# MoteinoMEGA.net
KiCad netlist of a schematic drawn in EAGLE
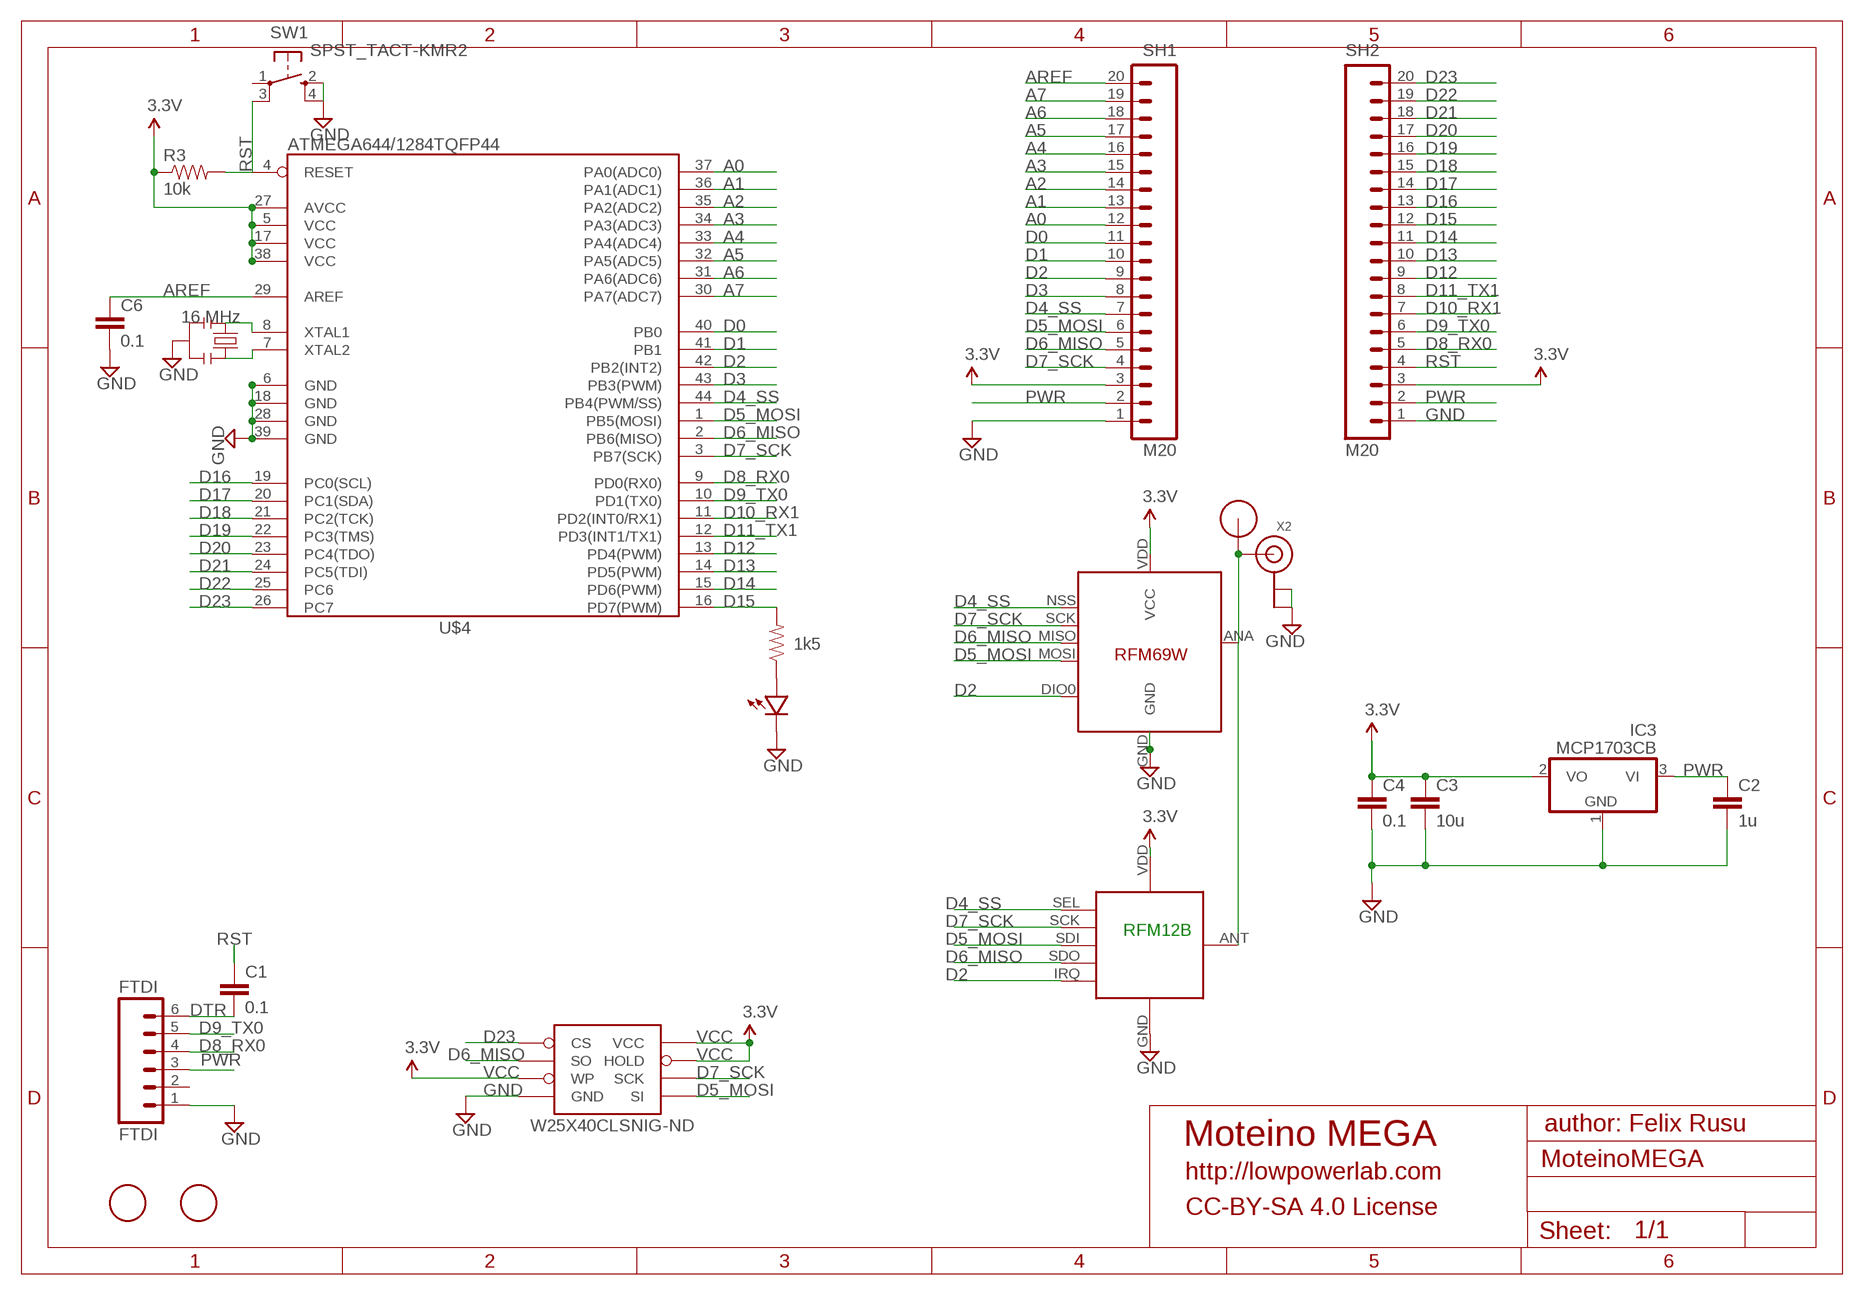
[diagram p0: schematic, sheet 1]

(export (version "E")
  (design (tool "Eeschema 10.0.6"))
  (components
    (comp (ref "C1")
      (value "0.1")
      (footprint "eagle-import:0603-CAP")
      (libsource (lib "eagle-import") (part "CAP0603-CAP"))
    )
    (comp (ref "C2")
      (value "1u")
      (footprint "eagle-import:0603-CAP")
      (libsource (lib "eagle-import") (part "CAP0603-CAP"))
    )
    (comp (ref "C3")
      (value "10u")
      (footprint "eagle-import:0805-CAP")
      (libsource (lib "eagle-import") (part "CAP0805-CAP"))
    )
    (comp (ref "C4")
      (value "0.1")
      (footprint "eagle-import:0603-CAP")
      (libsource (lib "eagle-import") (part "CAP0603-CAP"))
    )
    (comp (ref "C6")
      (value "0.1")
      (footprint "eagle-import:0603-CAP")
      (libsource (lib "eagle-import") (part "CAP0603-CAP"))
    )
    (comp (ref "FTDI")
      (value "FTDI")
      (footprint "eagle-import:1X06")
      (libsource (lib "eagle-import") (part "M06SIP"))
    )
    (comp (ref "IC3")
      (value "MCP1703CB")
      (footprint "eagle-import:SOT23")
      (libsource (lib "eagle-import") (part "MCP1703CB"))
    )
    (comp (ref "R2")
      (value "1k5")
      (footprint "eagle-import:0603-RES")
      (libsource (lib "eagle-import") (part "RESISTOR0603-RES"))
    )
    (comp (ref "R3")
      (value "10k")
      (footprint "eagle-import:0603-RES")
      (libsource (lib "eagle-import") (part "RESISTOR0603-RES"))
    )
    (comp (ref "RFM12B")
      (value "RFM12B_MINPADS")
      (footprint "eagle-import:RFM12B-MINPADS")
      (libsource (lib "eagle-import") (part "RFM12B_MINPADS"))
    )
    (comp (ref "SH1")
      (value "M20")
      (footprint "eagle-import:1X20")
      (libsource (lib "eagle-import") (part "M20"))
    )
    (comp (ref "SH2")
      (value "M20")
      (footprint "eagle-import:1X20")
      (libsource (lib "eagle-import") (part "M20"))
    )
    (comp (ref "SW1")
      (value "SPST_TACT-KMR2")
      (footprint "eagle-import:KMR2")
      (libsource (lib "eagle-import") (part "SPST_TACT-KMR2"))
    )
    (comp (ref "U$1")
      (value "RFM12B_ANTENNA")
      (footprint "eagle-import:RFM12B-ANTENNA")
      (libsource (lib "eagle-import") (part "RFM12B_ANTENNA"))
    )
    (comp (ref "U$2")
      (value "FIDUCIAL")
      (footprint "eagle-import:FIDUCIAL_1MM")
      (libsource (lib "eagle-import") (part "FIDUCIAL"))
    )
    (comp (ref "U$4")
      (value "ATMEGA644/1284TQFP44")
      (footprint "eagle-import:TQFP44")
      (libsource (lib "eagle-import") (part "ATMEGA644/1284TQFP44"))
    )
    (comp (ref "U$5")
      (value "RFM69")
      (footprint "eagle-import:RFM69W-MINPADS")
      (libsource (lib "eagle-import") (part "RFM69"))
    )
    (comp (ref "U$6")
      (value "LED0603")
      (footprint "eagle-import:0603-LED")
      (libsource (lib "eagle-import") (part "LED0603"))
    )
    (comp (ref "U$7")
      (value "FIDUCIAL")
      (footprint "eagle-import:FIDUCIAL_1MM")
      (libsource (lib "eagle-import") (part "FIDUCIAL"))
    )
    (comp (ref "W25X40CLSNIG-ND")
      (value "AT25F512BWIDE_5.3MM")
      (footprint "eagle-import:SO08WIDE")
      (libsource (lib "eagle-import") (part "AT25F512BWIDE_5.3MM"))
    )
    (comp (ref "X1")
      (value "16 MHz")
      (footprint "eagle-import:RESONATOR-SMD")
      (libsource (lib "eagle-import") (part "RESONATORSMD"))
    )
    (comp (ref "X2")
      (value "ANTENNA_U.FL")
      (footprint "eagle-import:U.FL")
      (libsource (lib "eagle-import") (part "ANTENNA_U.FL"))
    )
  )
  (nets
    (net (code "1") (name "/A0") (class "Default")
      (node (ref "SH1") (pin "12") (pinfunction "12_12") (pintype "passive"))
      (node (ref "U$4") (pin "37") (pinfunction "PA0(ADC0)_37") (pintype "bidirectional"))
    )
    (net (code "2") (name "/A1") (class "Default")
      (node (ref "SH1") (pin "13") (pinfunction "13_13") (pintype "passive"))
      (node (ref "U$4") (pin "36") (pinfunction "PA1(ADC1)_36") (pintype "bidirectional"))
    )
    (net (code "3") (name "/A2") (class "Default")
      (node (ref "SH1") (pin "14") (pinfunction "14_14") (pintype "passive"))
      (node (ref "U$4") (pin "35") (pinfunction "PA2(ADC2)_35") (pintype "bidirectional"))
    )
    (net (code "4") (name "/A3") (class "Default")
      (node (ref "SH1") (pin "15") (pinfunction "15_15") (pintype "passive"))
      (node (ref "U$4") (pin "34") (pinfunction "PA3(ADC3)_34") (pintype "bidirectional"))
    )
    (net (code "5") (name "/A4") (class "Default")
      (node (ref "SH1") (pin "16") (pinfunction "16_16") (pintype "passive"))
      (node (ref "U$4") (pin "33") (pinfunction "PA4(ADC4)_33") (pintype "bidirectional"))
    )
    (net (code "6") (name "/A5") (class "Default")
      (node (ref "SH1") (pin "17") (pinfunction "17_17") (pintype "passive"))
      (node (ref "U$4") (pin "32") (pinfunction "PA5(ADC5)_32") (pintype "bidirectional"))
    )
    (net (code "7") (name "/A6") (class "Default")
      (node (ref "SH1") (pin "18") (pinfunction "18_18") (pintype "passive"))
      (node (ref "U$4") (pin "31") (pinfunction "PA6(ADC6)_31") (pintype "bidirectional"))
    )
    (net (code "8") (name "/A7") (class "Default")
      (node (ref "SH1") (pin "19") (pinfunction "19_19") (pintype "passive"))
      (node (ref "U$4") (pin "30") (pinfunction "PA7(ADC7)_30") (pintype "bidirectional"))
    )
    (net (code "9") (name "/AREF") (class "Default")
      (node (ref "C6") (pin "1") (pinfunction "1_1") (pintype "passive"))
      (node (ref "SH1") (pin "20") (pinfunction "20_20") (pintype "passive"))
      (node (ref "U$4") (pin "29") (pinfunction "AREF_29") (pintype "bidirectional"))
    )
    (net (code "10") (name "/D0") (class "Default")
      (node (ref "SH1") (pin "11") (pinfunction "11_11") (pintype "passive"))
      (node (ref "U$4") (pin "40") (pinfunction "PB0_40") (pintype "bidirectional"))
    )
    (net (code "11") (name "/D1") (class "Default")
      (node (ref "SH1") (pin "10") (pinfunction "10_10") (pintype "passive"))
      (node (ref "U$4") (pin "41") (pinfunction "PB1_41") (pintype "bidirectional"))
    )
    (net (code "12") (name "/D2") (class "Default")
      (node (ref "RFM12B") (pin "IRQ") (pinfunction "IRQ_IRQ") (pintype "bidirectional"))
      (node (ref "SH1") (pin "9") (pinfunction "9_9") (pintype "passive"))
      (node (ref "U$4") (pin "42") (pinfunction "PB2(INT2)_42") (pintype "bidirectional"))
      (node (ref "U$5") (pin "DIO0") (pinfunction "DIO0_DIO0") (pintype "open_collector"))
    )
    (net (code "13") (name "/D3") (class "Default")
      (node (ref "SH1") (pin "8") (pinfunction "8_8") (pintype "passive"))
      (node (ref "U$4") (pin "43") (pinfunction "PB3(PWM)_43") (pintype "bidirectional"))
    )
    (net (code "14") (name "/D4_SS") (class "Default")
      (node (ref "RFM12B") (pin "SEL") (pinfunction "SEL_SEL") (pintype "bidirectional"))
      (node (ref "SH1") (pin "7") (pinfunction "7_7") (pintype "passive"))
      (node (ref "U$4") (pin "44") (pinfunction "PB4(PWM/SS)_44") (pintype "bidirectional"))
      (node (ref "U$5") (pin "NSS") (pinfunction "SEL_NSS") (pintype "input"))
    )
    (net (code "15") (name "/D5_MOSI") (class "Default")
      (node (ref "RFM12B") (pin "SDI") (pinfunction "SDI/MOSI_SDI") (pintype "bidirectional"))
      (node (ref "SH1") (pin "6") (pinfunction "6_6") (pintype "passive"))
      (node (ref "U$4") (pin "1") (pinfunction "PB5(MOSI)_1") (pintype "bidirectional"))
      (node (ref "U$5") (pin "MOSI") (pinfunction "MOSI_MOSI") (pintype "output"))
      (node (ref "W25X40CLSNIG-ND") (pin "5") (pinfunction "SI_5") (pintype "bidirectional"))
    )
    (net (code "16") (name "/D6_MISO") (class "Default")
      (node (ref "RFM12B") (pin "SDO") (pinfunction "SDO/MISO_SDO") (pintype "bidirectional"))
      (node (ref "SH1") (pin "5") (pinfunction "5_5") (pintype "passive"))
      (node (ref "U$4") (pin "2") (pinfunction "PB6(MISO)_2") (pintype "bidirectional"))
      (node (ref "U$5") (pin "MISO") (pinfunction "MISO_MISO") (pintype "input"))
      (node (ref "W25X40CLSNIG-ND") (pin "2") (pinfunction "SO_2") (pintype "bidirectional"))
    )
    (net (code "17") (name "/D7_SCK") (class "Default")
      (node (ref "RFM12B") (pin "SCK") (pinfunction "SCK_SCK") (pintype "bidirectional"))
      (node (ref "SH1") (pin "4") (pinfunction "4_4") (pintype "passive"))
      (node (ref "U$4") (pin "3") (pinfunction "PB7(SCK)_3") (pintype "bidirectional"))
      (node (ref "U$5") (pin "SCK") (pinfunction "SCK_SCK") (pintype "input"))
      (node (ref "W25X40CLSNIG-ND") (pin "6") (pinfunction "SCK_6") (pintype "bidirectional"))
    )
    (net (code "18") (name "/D8_RX0") (class "Default")
      (node (ref "FTDI") (pin "4") (pinfunction "4_4") (pintype "passive"))
      (node (ref "SH2") (pin "5") (pinfunction "5_5") (pintype "passive"))
      (node (ref "U$4") (pin "9") (pinfunction "PD0(RX0)_9") (pintype "bidirectional"))
    )
    (net (code "19") (name "/D9_TX0") (class "Default")
      (node (ref "FTDI") (pin "5") (pinfunction "5_5") (pintype "passive"))
      (node (ref "SH2") (pin "6") (pinfunction "6_6") (pintype "passive"))
      (node (ref "U$4") (pin "10") (pinfunction "PD1(TX0)_10") (pintype "bidirectional"))
    )
    (net (code "20") (name "/D10_RX1") (class "Default")
      (node (ref "SH2") (pin "7") (pinfunction "7_7") (pintype "passive"))
      (node (ref "U$4") (pin "11") (pinfunction "PD2(INT0/RX1)_11") (pintype "bidirectional"))
    )
    (net (code "21") (name "/D11_TX1") (class "Default")
      (node (ref "SH2") (pin "8") (pinfunction "8_8") (pintype "passive"))
      (node (ref "U$4") (pin "12") (pinfunction "PD3(INT1/TX1)_12") (pintype "bidirectional"))
    )
    (net (code "22") (name "/D12") (class "Default")
      (node (ref "SH2") (pin "9") (pinfunction "9_9") (pintype "passive"))
      (node (ref "U$4") (pin "13") (pinfunction "PD4(PWM)_13") (pintype "bidirectional"))
    )
    (net (code "23") (name "/D13") (class "Default")
      (node (ref "SH2") (pin "10") (pinfunction "10_10") (pintype "passive"))
      (node (ref "U$4") (pin "14") (pinfunction "PD5(PWM)_14") (pintype "bidirectional"))
    )
    (net (code "24") (name "/D14") (class "Default")
      (node (ref "SH2") (pin "11") (pinfunction "11_11") (pintype "passive"))
      (node (ref "U$4") (pin "15") (pinfunction "PD6(PWM)_15") (pintype "bidirectional"))
    )
    (net (code "25") (name "/D15") (class "Default")
      (node (ref "R2") (pin "2") (pinfunction "2_2") (pintype "passive"))
      (node (ref "SH2") (pin "12") (pinfunction "12_12") (pintype "passive"))
      (node (ref "U$4") (pin "16") (pinfunction "PD7(PWM)_16") (pintype "bidirectional"))
    )
    (net (code "26") (name "/D16") (class "Default")
      (node (ref "SH2") (pin "13") (pinfunction "13_13") (pintype "passive"))
      (node (ref "U$4") (pin "19") (pinfunction "PC0(SCL)_19") (pintype "bidirectional"))
    )
    (net (code "27") (name "/D17") (class "Default")
      (node (ref "SH2") (pin "14") (pinfunction "14_14") (pintype "passive"))
      (node (ref "U$4") (pin "20") (pinfunction "PC1(SDA)_20") (pintype "bidirectional"))
    )
    (net (code "28") (name "/D18") (class "Default")
      (node (ref "SH2") (pin "15") (pinfunction "15_15") (pintype "passive"))
      (node (ref "U$4") (pin "21") (pinfunction "PC2(TCK)_21") (pintype "bidirectional"))
    )
    (net (code "29") (name "/D19") (class "Default")
      (node (ref "SH2") (pin "16") (pinfunction "16_16") (pintype "passive"))
      (node (ref "U$4") (pin "22") (pinfunction "PC3(TMS)_22") (pintype "bidirectional"))
    )
    (net (code "30") (name "/D20") (class "Default")
      (node (ref "SH2") (pin "17") (pinfunction "17_17") (pintype "passive"))
      (node (ref "U$4") (pin "23") (pinfunction "PC4(TDO)_23") (pintype "bidirectional"))
    )
    (net (code "31") (name "/D21") (class "Default")
      (node (ref "SH2") (pin "18") (pinfunction "18_18") (pintype "passive"))
      (node (ref "U$4") (pin "24") (pinfunction "PC5(TDI)_24") (pintype "bidirectional"))
    )
    (net (code "32") (name "/D22") (class "Default")
      (node (ref "SH2") (pin "19") (pinfunction "19_19") (pintype "passive"))
      (node (ref "U$4") (pin "25") (pinfunction "PC6_25") (pintype "bidirectional"))
    )
    (net (code "33") (name "/D23") (class "Default")
      (node (ref "SH2") (pin "20") (pinfunction "20_20") (pintype "passive"))
      (node (ref "U$4") (pin "26") (pinfunction "PC7_26") (pintype "bidirectional"))
      (node (ref "W25X40CLSNIG-ND") (pin "1") (pinfunction "CS_1") (pintype "bidirectional"))
    )
    (net (code "34") (name "/DTR") (class "Default")
      (node (ref "C1") (pin "2") (pinfunction "2_2") (pintype "passive"))
      (node (ref "FTDI") (pin "6") (pinfunction "6_6") (pintype "passive"))
    )
    (net (code "35") (name "/PWR") (class "Default")
      (node (ref "C2") (pin "1") (pinfunction "1_1") (pintype "passive"))
      (node (ref "FTDI") (pin "3") (pinfunction "3_3") (pintype "passive"))
      (node (ref "IC3") (pin "3") (pinfunction "VI_3") (pintype "input"))
      (node (ref "SH1") (pin "2") (pinfunction "2_2") (pintype "passive"))
      (node (ref "SH2") (pin "2") (pinfunction "2_2") (pintype "passive"))
    )
    (net (code "36") (name "/RST") (class "Default")
      (node (ref "C1") (pin "1") (pinfunction "1_1") (pintype "passive"))
      (node (ref "R3") (pin "2") (pinfunction "2_2") (pintype "passive"))
      (node (ref "SH2") (pin "4") (pinfunction "4_4") (pintype "passive"))
      (node (ref "SW1") (pin "3") (pinfunction "P1_3") (pintype "passive"))
      (node (ref "U$4") (pin "4") (pinfunction "RESET_4") (pintype "bidirectional"))
    )
    (net (code "37") (name "3.3V") (class "Default")
      (node (ref "C3") (pin "1") (pinfunction "1_1") (pintype "passive"))
      (node (ref "C4") (pin "1") (pinfunction "1_1") (pintype "passive"))
      (node (ref "IC3") (pin "2") (pinfunction "VO_2") (pintype "passive"))
      (node (ref "R3") (pin "1") (pinfunction "1_1") (pintype "passive"))
      (node (ref "RFM12B") (pin "VDD") (pinfunction "VDD_VDD") (pintype "bidirectional"))
      (node (ref "SH1") (pin "3") (pinfunction "3_3") (pintype "passive"))
      (node (ref "SH2") (pin "3") (pinfunction "3_3") (pintype "passive"))
      (node (ref "U$4") (pin "17") (pinfunction "VCC_17") (pintype "bidirectional"))
      (node (ref "U$4") (pin "27") (pinfunction "AVCC_27") (pintype "bidirectional"))
      (node (ref "U$4") (pin "38") (pinfunction "VCC_38") (pintype "bidirectional"))
      (node (ref "U$4") (pin "5") (pinfunction "VCC_5") (pintype "bidirectional"))
      (node (ref "U$5") (pin "VDD") (pinfunction "VCC_VDD") (pintype "power_in"))
      (node (ref "W25X40CLSNIG-ND") (pin "3") (pinfunction "WP_3") (pintype "bidirectional"))
      (node (ref "W25X40CLSNIG-ND") (pin "7") (pinfunction "HOLD_7") (pintype "bidirectional"))
      (node (ref "W25X40CLSNIG-ND") (pin "8") (pinfunction "VCC_8") (pintype "bidirectional"))
    )
    (net (code "38") (name "GND") (class "Default")
      (node (ref "C2") (pin "2") (pinfunction "2_2") (pintype "passive"))
      (node (ref "C3") (pin "2") (pinfunction "2_2") (pintype "passive"))
      (node (ref "C4") (pin "2") (pinfunction "2_2") (pintype "passive"))
      (node (ref "C6") (pin "2") (pinfunction "2_2") (pintype "passive"))
      (node (ref "FTDI") (pin "1") (pinfunction "1_1") (pintype "passive"))
      (node (ref "IC3") (pin "1") (pinfunction "GND_1") (pintype "passive"))
      (node (ref "RFM12B") (pin "GND") (pinfunction "GND_GND") (pintype "bidirectional"))
      (node (ref "SH1") (pin "1") (pinfunction "1_1") (pintype "passive"))
      (node (ref "SH2") (pin "1") (pinfunction "1_1") (pintype "passive"))
      (node (ref "SW1") (pin "2") (pinfunction "S_2") (pintype "passive"))
      (node (ref "SW1") (pin "4") (pinfunction "S1_4") (pintype "passive"))
      (node (ref "U$4") (pin "18") (pinfunction "GND_18") (pintype "bidirectional"))
      (node (ref "U$4") (pin "28") (pinfunction "GND_28") (pintype "bidirectional"))
      (node (ref "U$4") (pin "39") (pinfunction "GND_39") (pintype "bidirectional"))
      (node (ref "U$4") (pin "6") (pinfunction "GND_6") (pintype "bidirectional"))
      (node (ref "U$5") (pin "GND") (pinfunction "GND_GND") (pintype "power_in"))
      (node (ref "U$6") (pin "MINUS") (pinfunction "MINUS_MINUS") (pintype "passive"))
      (node (ref "W25X40CLSNIG-ND") (pin "4") (pinfunction "GND_4") (pintype "bidirectional"))
      (node (ref "X1") (pin "2") (pinfunction "2_2") (pintype "passive"))
      (node (ref "X2") (pin "1") (pinfunction "GND_1") (pintype "passive"))
      (node (ref "X2") (pin "2") (pinfunction "GND_2") (pintype "passive"))
    )
    (net (code "39") (name "Net-(R2-Pad1)") (class "Default")
      (node (ref "R2") (pin "1") (pinfunction "1_1") (pintype "passive"))
      (node (ref "U$6") (pin "PLUS") (pinfunction "PLUS_PLUS") (pintype "passive"))
    )
    (net (code "40") (name "Net-(U$1-1)") (class "Default")
      (node (ref "RFM12B") (pin "ANT") (pinfunction "ANT_ANT") (pintype "bidirectional"))
      (node (ref "U$1") (pin "P$1") (pinfunction "1_P$1") (pintype "bidirectional"))
      (node (ref "U$5") (pin "ANA") (pinfunction "ANT_ANA") (pintype "passive"))
      (node (ref "X2") (pin "3") (pinfunction "SIGNAL_3") (pintype "passive"))
    )
    (net (code "41") (name "Net-(U$4-XTAL1)") (class "Default")
      (node (ref "U$4") (pin "8") (pinfunction "XTAL1_8") (pintype "bidirectional"))
      (node (ref "X1") (pin "1") (pinfunction "1_1") (pintype "passive"))
    )
    (net (code "42") (name "Net-(U$4-XTAL2)") (class "Default")
      (node (ref "U$4") (pin "7") (pinfunction "XTAL2_7") (pintype "bidirectional"))
      (node (ref "X1") (pin "3") (pinfunction "3_3") (pintype "passive"))
    )
    (net (code "43") (name "unconnected-(FTDI-Pad2)") (class "Default")
      (node (ref "FTDI") (pin "2") (pinfunction "2_2") (pintype "passive"))
    )
    (net (code "44") (name "unconnected-(SW1-P-Pad1)") (class "Default")
      (node (ref "SW1") (pin "1") (pinfunction "P_1") (pintype "passive"))
    )
  )
)
